# HF_front.net
KiCad netlist of a schematic drawn in EAGLE
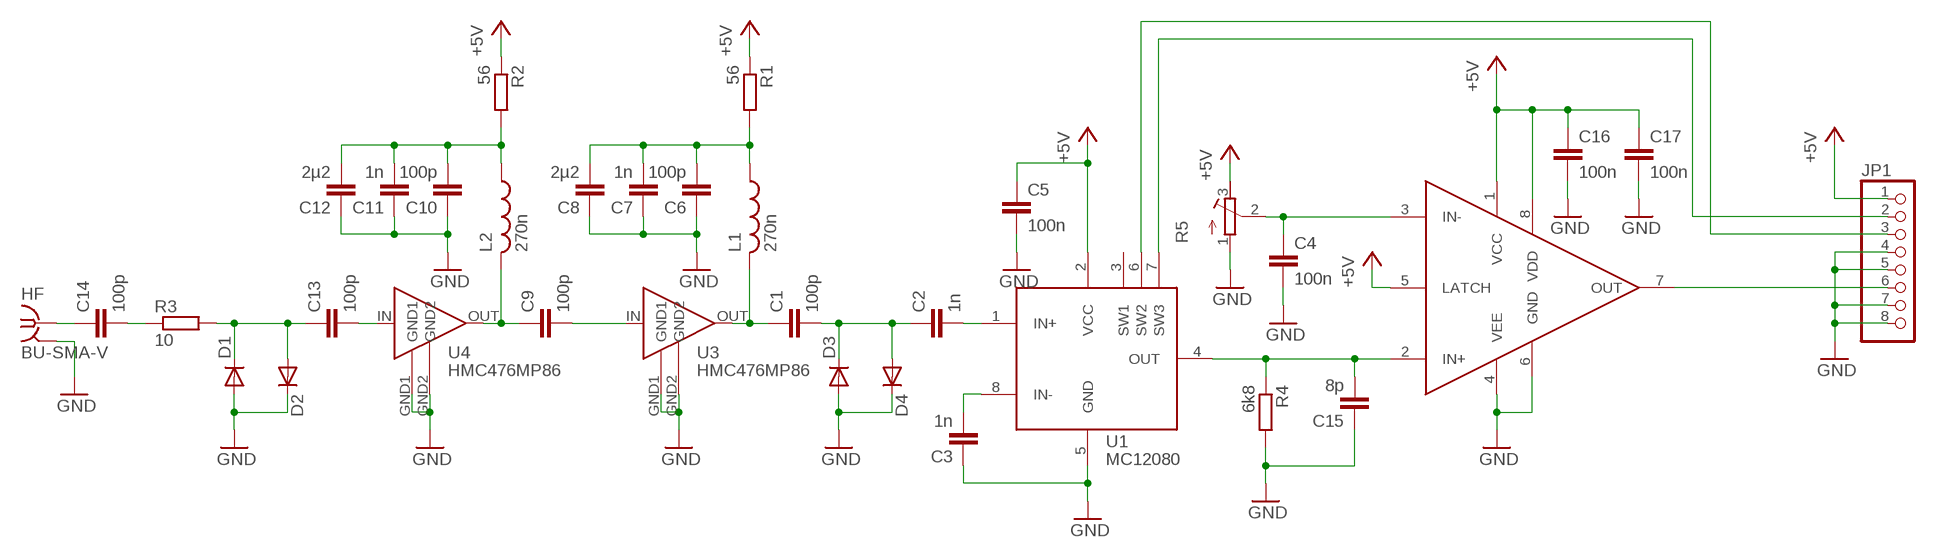
[diagram p0: schematic, sheet 1]

(export (version "E")
  (design (tool "Eeschema 10.0.6"))
  (components
    (comp (ref "C1")
      (value "100p")
      (footprint "eagle-import:C0603")
      (libsource (lib "eagle-import") (part "C-EUC0603"))
    )
    (comp (ref "C2")
      (value "1n")
      (footprint "eagle-import:C0603")
      (libsource (lib "eagle-import") (part "C-EUC0603"))
    )
    (comp (ref "C3")
      (value "1n")
      (footprint "eagle-import:C0603")
      (libsource (lib "eagle-import") (part "C-EUC0603"))
    )
    (comp (ref "C4")
      (value "100n")
      (footprint "eagle-import:C0603")
      (libsource (lib "eagle-import") (part "C-EUC0603"))
    )
    (comp (ref "C5")
      (value "100n")
      (footprint "eagle-import:C0603")
      (libsource (lib "eagle-import") (part "C-EUC0603"))
    )
    (comp (ref "C6")
      (value "100p")
      (footprint "eagle-import:C0603")
      (libsource (lib "eagle-import") (part "C-EUC0603"))
    )
    (comp (ref "C7")
      (value "1n")
      (footprint "eagle-import:C0603")
      (libsource (lib "eagle-import") (part "C-EUC0603"))
    )
    (comp (ref "C8")
      (value "2µ2")
      (footprint "eagle-import:C0603")
      (libsource (lib "eagle-import") (part "C-EUC0603"))
    )
    (comp (ref "C9")
      (value "100p")
      (footprint "eagle-import:C0603")
      (libsource (lib "eagle-import") (part "C-EUC0603"))
    )
    (comp (ref "C10")
      (value "100p")
      (footprint "eagle-import:C0603")
      (libsource (lib "eagle-import") (part "C-EUC0603"))
    )
    (comp (ref "C11")
      (value "1n")
      (footprint "eagle-import:C0603")
      (libsource (lib "eagle-import") (part "C-EUC0603"))
    )
    (comp (ref "C12")
      (value "2µ2")
      (footprint "eagle-import:C0603")
      (libsource (lib "eagle-import") (part "C-EUC0603"))
    )
    (comp (ref "C13")
      (value "100p")
      (footprint "eagle-import:C0603")
      (libsource (lib "eagle-import") (part "C-EUC0603"))
    )
    (comp (ref "C14")
      (value "100p")
      (footprint "eagle-import:C0603")
      (libsource (lib "eagle-import") (part "C-EUC0603"))
    )
    (comp (ref "C15")
      (value "8p")
      (footprint "eagle-import:C0603")
      (libsource (lib "eagle-import") (part "C-EUC0603"))
    )
    (comp (ref "C16")
      (value "100n")
      (footprint "eagle-import:C0603")
      (libsource (lib "eagle-import") (part "C-EUC0603"))
    )
    (comp (ref "C17")
      (value "100n")
      (footprint "eagle-import:C0603")
      (libsource (lib "eagle-import") (part "C-EUC0603"))
    )
    (comp (ref "D1")
      (value "DIODE-SOD323-W")
      (footprint "eagle-import:SOD323-W")
      (libsource (lib "eagle-import") (part "DIODE-SOD323-W"))
    )
    (comp (ref "D2")
      (value "DIODE-SOD323-W")
      (footprint "eagle-import:SOD323-W")
      (libsource (lib "eagle-import") (part "DIODE-SOD323-W"))
    )
    (comp (ref "D3")
      (value "DIODE-SOD323-W")
      (footprint "eagle-import:SOD323-W")
      (libsource (lib "eagle-import") (part "DIODE-SOD323-W"))
    )
    (comp (ref "D4")
      (value "DIODE-SOD323-W")
      (footprint "eagle-import:SOD323-W")
      (libsource (lib "eagle-import") (part "DIODE-SOD323-W"))
    )
    (comp (ref "HF")
      (value "BU-SMA-V")
      (footprint "eagle-import:BU-SMA-V")
      (libsource (lib "eagle-import") (part "BU-SMA-V"))
    )
    (comp (ref "JP1")
      (value "PINHD-1X8")
      (footprint "eagle-import:1X08")
      (libsource (lib "eagle-import") (part "PINHD-1X8"))
    )
    (comp (ref "L1")
      (value "270n")
      (footprint "eagle-import:R0603")
      (libsource (lib "eagle-import") (part "INDUCTOR0603"))
    )
    (comp (ref "L2")
      (value "270n")
      (footprint "eagle-import:R0603")
      (libsource (lib "eagle-import") (part "INDUCTOR0603"))
    )
    (comp (ref "R1")
      (value "56")
      (footprint "eagle-import:R0603")
      (libsource (lib "eagle-import") (part "R-EU_R0603"))
    )
    (comp (ref "R2")
      (value "56")
      (footprint "eagle-import:R0603")
      (libsource (lib "eagle-import") (part "R-EU_R0603"))
    )
    (comp (ref "R3")
      (value "10")
      (footprint "eagle-import:R0603")
      (libsource (lib "eagle-import") (part "R-EU_R0603"))
    )
    (comp (ref "R4")
      (value "6k8")
      (footprint "eagle-import:R0603")
      (libsource (lib "eagle-import") (part "R-EU_R0603"))
    )
    (comp (ref "R5")
      (value "R-TRIMM64W")
      (footprint "eagle-import:RTRIM64W")
      (libsource (lib "eagle-import") (part "R-TRIMM64W"))
    )
    (comp (ref "U1")
      (value "MC12080")
      (footprint "eagle-import:SOIC8")
      (libsource (lib "eagle-import") (part "MC12080"))
    )
    (comp (ref "U2")
      (value "MAX9203")
      (footprint "eagle-import:SOIC8")
      (libsource (lib "eagle-import") (part "MAX9203"))
    )
    (comp (ref "U3")
      (value "HMC476MP86")
      (footprint "eagle-import:MICRO-X")
      (libsource (lib "eagle-import") (part "HMC476MP86"))
    )
    (comp (ref "U4")
      (value "HMC476MP86")
      (footprint "eagle-import:MICRO-X")
      (libsource (lib "eagle-import") (part "HMC476MP86"))
    )
  )
  (nets
    (net (code "1") (name "+5V") (class "Default")
      (node (ref "C16") (pin "1") (pinfunction "1_1") (pintype "passive"))
      (node (ref "C17") (pin "1") (pinfunction "1_1") (pintype "passive"))
      (node (ref "C5") (pin "1") (pinfunction "1_1") (pintype "passive"))
      (node (ref "JP1") (pin "1") (pinfunction "1_1") (pintype "passive"))
      (node (ref "R1") (pin "1") (pinfunction "1_1") (pintype "passive"))
      (node (ref "R2") (pin "1") (pinfunction "1_1") (pintype "passive"))
      (node (ref "R5") (pin "3") (pinfunction "A_3") (pintype "passive"))
      (node (ref "U1") (pin "2") (pinfunction "VCC_2") (pintype "bidirectional"))
      (node (ref "U2") (pin "1") (pinfunction "VCC_1") (pintype "bidirectional"))
      (node (ref "U2") (pin "5") (pinfunction "LATCH_5") (pintype "bidirectional"))
      (node (ref "U2") (pin "8") (pinfunction "VDD_8") (pintype "bidirectional"))
    )
    (net (code "2") (name "GND") (class "Default")
      (node (ref "C10") (pin "1") (pinfunction "1_1") (pintype "passive"))
      (node (ref "C11") (pin "1") (pinfunction "1_1") (pintype "passive"))
      (node (ref "C12") (pin "1") (pinfunction "1_1") (pintype "passive"))
      (node (ref "C15") (pin "1") (pinfunction "1_1") (pintype "passive"))
      (node (ref "C16") (pin "2") (pinfunction "2_2") (pintype "passive"))
      (node (ref "C17") (pin "2") (pinfunction "2_2") (pintype "passive"))
      (node (ref "C3") (pin "1") (pinfunction "1_1") (pintype "passive"))
      (node (ref "C4") (pin "2") (pinfunction "2_2") (pintype "passive"))
      (node (ref "C5") (pin "2") (pinfunction "2_2") (pintype "passive"))
      (node (ref "C6") (pin "1") (pinfunction "1_1") (pintype "passive"))
      (node (ref "C7") (pin "1") (pinfunction "1_1") (pintype "passive"))
      (node (ref "C8") (pin "1") (pinfunction "1_1") (pintype "passive"))
      (node (ref "D1") (pin "A") (pinfunction "A_A") (pintype "passive"))
      (node (ref "D2") (pin "C") (pinfunction "C_C") (pintype "passive"))
      (node (ref "D3") (pin "A") (pinfunction "A_A") (pintype "passive"))
      (node (ref "D4") (pin "C") (pinfunction "C_C") (pintype "passive"))
      (node (ref "HF") (pin "2") (pinfunction "2_2") (pintype "passive"))
      (node (ref "HF") (pin "3") (pinfunction "2_3") (pintype "passive"))
      (node (ref "HF") (pin "4") (pinfunction "2_4") (pintype "passive"))
      (node (ref "HF") (pin "5") (pinfunction "2_5") (pintype "passive"))
      (node (ref "JP1") (pin "4") (pinfunction "4_4") (pintype "passive"))
      (node (ref "JP1") (pin "5") (pinfunction "5_5") (pintype "passive"))
      (node (ref "JP1") (pin "7") (pinfunction "7_7") (pintype "passive"))
      (node (ref "JP1") (pin "8") (pinfunction "8_8") (pintype "passive"))
      (node (ref "R4") (pin "2") (pinfunction "2_2") (pintype "passive"))
      (node (ref "R5") (pin "1") (pinfunction "E_1") (pintype "passive"))
      (node (ref "U1") (pin "5") (pinfunction "GND_5") (pintype "bidirectional"))
      (node (ref "U2") (pin "4") (pinfunction "VEE_4") (pintype "bidirectional"))
      (node (ref "U2") (pin "6") (pinfunction "GND_6") (pintype "bidirectional"))
      (node (ref "U3") (pin "GND1") (pinfunction "GND1_GND1") (pintype "power_in"))
      (node (ref "U3") (pin "GND2") (pinfunction "GND2_GND2") (pintype "power_in"))
      (node (ref "U4") (pin "GND1") (pinfunction "GND1_GND1") (pintype "power_in"))
      (node (ref "U4") (pin "GND2") (pinfunction "GND2_GND2") (pintype "power_in"))
    )
    (net (code "3") (name "Net-(C1-Pad1)") (class "Default")
      (node (ref "C1") (pin "1") (pinfunction "1_1") (pintype "passive"))
      (node (ref "L1") (pin "2") (pinfunction "2_2") (pintype "passive"))
      (node (ref "U3") (pin "OUT") (pinfunction "OUT_OUT") (pintype "output"))
    )
    (net (code "4") (name "Net-(C1-Pad2)") (class "Default")
      (node (ref "C1") (pin "2") (pinfunction "2_2") (pintype "passive"))
      (node (ref "C2") (pin "1") (pinfunction "1_1") (pintype "passive"))
      (node (ref "D3") (pin "C") (pinfunction "C_C") (pintype "passive"))
      (node (ref "D4") (pin "A") (pinfunction "A_A") (pintype "passive"))
    )
    (net (code "5") (name "Net-(C6-Pad2)") (class "Default")
      (node (ref "C6") (pin "2") (pinfunction "2_2") (pintype "passive"))
      (node (ref "C7") (pin "2") (pinfunction "2_2") (pintype "passive"))
      (node (ref "C8") (pin "2") (pinfunction "2_2") (pintype "passive"))
      (node (ref "L1") (pin "1") (pinfunction "1_1") (pintype "passive"))
      (node (ref "R1") (pin "2") (pinfunction "2_2") (pintype "passive"))
    )
    (net (code "6") (name "Net-(C9-Pad1)") (class "Default")
      (node (ref "C9") (pin "1") (pinfunction "1_1") (pintype "passive"))
      (node (ref "L2") (pin "2") (pinfunction "2_2") (pintype "passive"))
      (node (ref "U4") (pin "OUT") (pinfunction "OUT_OUT") (pintype "output"))
    )
    (net (code "7") (name "Net-(C9-Pad2)") (class "Default")
      (node (ref "C9") (pin "2") (pinfunction "2_2") (pintype "passive"))
      (node (ref "U3") (pin "IN") (pinfunction "IN_IN") (pintype "input"))
    )
    (net (code "8") (name "Net-(C10-Pad2)") (class "Default")
      (node (ref "C10") (pin "2") (pinfunction "2_2") (pintype "passive"))
      (node (ref "C11") (pin "2") (pinfunction "2_2") (pintype "passive"))
      (node (ref "C12") (pin "2") (pinfunction "2_2") (pintype "passive"))
      (node (ref "L2") (pin "1") (pinfunction "1_1") (pintype "passive"))
      (node (ref "R2") (pin "2") (pinfunction "2_2") (pintype "passive"))
    )
    (net (code "9") (name "Net-(C13-Pad1)") (class "Default")
      (node (ref "C13") (pin "1") (pinfunction "1_1") (pintype "passive"))
      (node (ref "D1") (pin "C") (pinfunction "C_C") (pintype "passive"))
      (node (ref "D2") (pin "A") (pinfunction "A_A") (pintype "passive"))
      (node (ref "R3") (pin "2") (pinfunction "2_2") (pintype "passive"))
    )
    (net (code "10") (name "Net-(C13-Pad2)") (class "Default")
      (node (ref "C13") (pin "2") (pinfunction "2_2") (pintype "passive"))
      (node (ref "U4") (pin "IN") (pinfunction "IN_IN") (pintype "input"))
    )
    (net (code "11") (name "Net-(C14-Pad1)") (class "Default")
      (node (ref "C14") (pin "1") (pinfunction "1_1") (pintype "passive"))
      (node (ref "HF") (pin "1") (pinfunction "1_1") (pintype "passive"))
    )
    (net (code "12") (name "Net-(C14-Pad2)") (class "Default")
      (node (ref "C14") (pin "2") (pinfunction "2_2") (pintype "passive"))
      (node (ref "R3") (pin "1") (pinfunction "1_1") (pintype "passive"))
    )
    (net (code "13") (name "Net-(R5-S)") (class "Default")
      (node (ref "C4") (pin "1") (pinfunction "1_1") (pintype "passive"))
      (node (ref "R5") (pin "2") (pinfunction "S_2") (pintype "passive"))
      (node (ref "U2") (pin "3") (pinfunction "IN-_3") (pintype "bidirectional"))
    )
    (net (code "14") (name "Net-(U1-IN+)") (class "Default")
      (node (ref "C2") (pin "2") (pinfunction "2_2") (pintype "passive"))
      (node (ref "U1") (pin "1") (pinfunction "IN+_1") (pintype "bidirectional"))
    )
    (net (code "15") (name "Net-(U1-IN-)") (class "Default")
      (node (ref "C3") (pin "2") (pinfunction "2_2") (pintype "passive"))
      (node (ref "U1") (pin "8") (pinfunction "IN-_8") (pintype "bidirectional"))
    )
    (net (code "16") (name "Net-(U1-OUT)") (class "Default")
      (node (ref "C15") (pin "2") (pinfunction "2_2") (pintype "passive"))
      (node (ref "R4") (pin "1") (pinfunction "1_1") (pintype "passive"))
      (node (ref "U1") (pin "4") (pinfunction "OUT_4") (pintype "bidirectional"))
      (node (ref "U2") (pin "2") (pinfunction "IN+_2") (pintype "bidirectional"))
    )
    (net (code "17") (name "Net-(U1-SW2)") (class "Default")
      (node (ref "JP1") (pin "3") (pinfunction "3_3") (pintype "passive"))
      (node (ref "U1") (pin "6") (pinfunction "SW2_6") (pintype "bidirectional"))
    )
    (net (code "18") (name "Net-(U1-SW3)") (class "Default")
      (node (ref "JP1") (pin "2") (pinfunction "2_2") (pintype "passive"))
      (node (ref "U1") (pin "7") (pinfunction "SW3_7") (pintype "bidirectional"))
    )
    (net (code "19") (name "Net-(U2-OUT)") (class "Default")
      (node (ref "JP1") (pin "6") (pinfunction "6_6") (pintype "passive"))
      (node (ref "U2") (pin "7") (pinfunction "OUT_7") (pintype "bidirectional"))
    )
    (net (code "20") (name "unconnected-(U1-SW1-Pad3)") (class "Default")
      (node (ref "U1") (pin "3") (pinfunction "SW1_3") (pintype "bidirectional"))
    )
  )
)
